# DigitalCarrierJack.net
KiCad netlist of a schematic drawn in Altium Designer
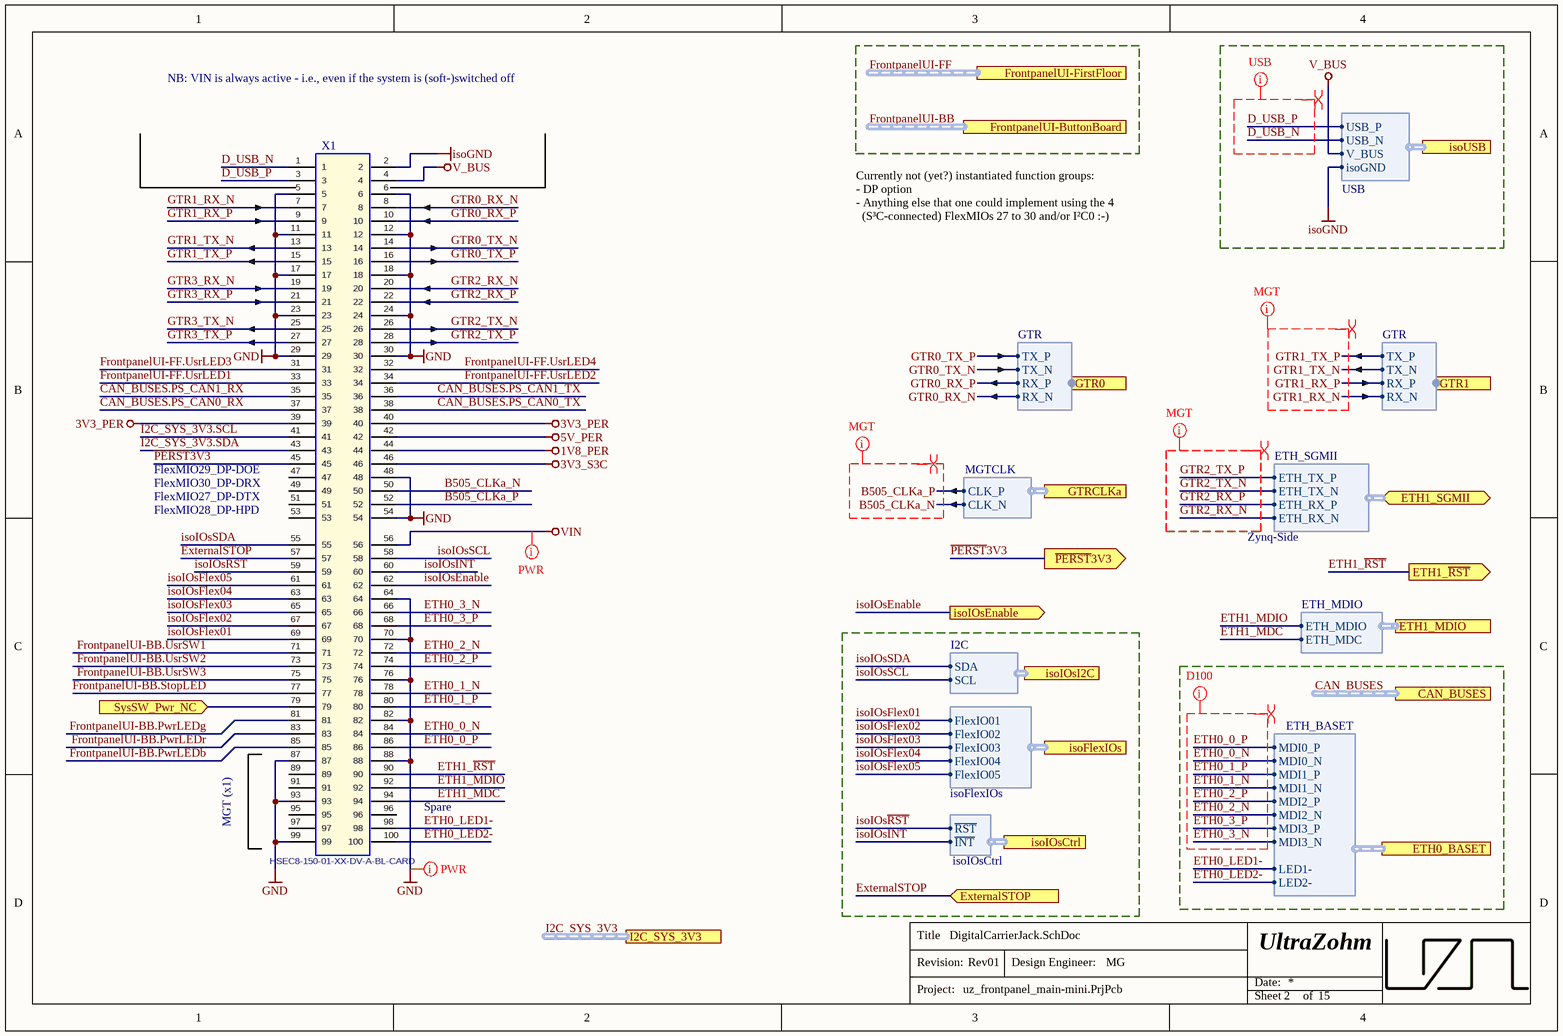
[diagram p0: DigitalCarrierJack.SchDoc]

(export (version "E")
  (design (tool "Eeschema 10.0.6"))
  (components
    (comp (ref "X1")
      (value "HSEC8-150-01-XX-DV-A-BL-CARD")
      (footprint "HSEC8-150-01-XX-DV-A-BL-CARD")
      (description "Mating Card Layout for HSEC8-150-01-XX-DV-A-BL")
      (fields (field (name "MANUFACTURER") "SAMTEC") (field (name "CREATED") "2018_04_23_AGeiger"))
      (libsource (lib "connectors") (part "HSEC8-150-01-XX-DV-A-BL-CARD"))
    )
  )
  (nets
    (net (code "14") (name "/B505_CLKa_N") (class "Default")
      (node (ref "X1") (pin "50") (pinfunction "50_50") (pintype "passive"))
    )
    (net (code "15") (name "/B505_CLKa_P") (class "Default")
      (node (ref "X1") (pin "52") (pinfunction "52_52") (pintype "passive"))
    )
    (net (code "16") (name "/CAN_BUSES.PS_CAN0_RX") (class "Default")
      (node (ref "X1") (pin "37") (pinfunction "37_37") (pintype "passive"))
    )
    (net (code "17") (name "/CAN_BUSES.PS_CAN0_TX") (class "Default")
      (node (ref "X1") (pin "38") (pinfunction "38_38") (pintype "passive"))
    )
    (net (code "18") (name "/CAN_BUSES.PS_CAN1_RX") (class "Default")
      (node (ref "X1") (pin "35") (pinfunction "35_35") (pintype "passive"))
    )
    (net (code "19") (name "/CAN_BUSES.PS_CAN1_TX") (class "Default")
      (node (ref "X1") (pin "36") (pinfunction "36_36") (pintype "passive"))
    )
    (net (code "20") (name "/D_USB_N") (class "Default")
      (node (ref "X1") (pin "1") (pinfunction "1_1") (pintype "passive"))
    )
    (net (code "21") (name "/D_USB_P") (class "Default")
      (node (ref "X1") (pin "3") (pinfunction "3_3") (pintype "passive"))
    )
    (net (code "22") (name "/ETH0_0_N") (class "Default")
      (node (ref "X1") (pin "84") (pinfunction "84_84") (pintype "passive"))
    )
    (net (code "23") (name "/ETH0_0_P") (class "Default")
      (node (ref "X1") (pin "86") (pinfunction "86_86") (pintype "passive"))
    )
    (net (code "24") (name "/ETH0_1_N") (class "Default")
      (node (ref "X1") (pin "78") (pinfunction "78_78") (pintype "passive"))
    )
    (net (code "25") (name "/ETH0_1_P") (class "Default")
      (node (ref "X1") (pin "80") (pinfunction "80_80") (pintype "passive"))
    )
    (net (code "26") (name "/ETH0_2_N") (class "Default")
      (node (ref "X1") (pin "72") (pinfunction "72_72") (pintype "passive"))
    )
    (net (code "27") (name "/ETH0_2_P") (class "Default")
      (node (ref "X1") (pin "74") (pinfunction "74_74") (pintype "passive"))
    )
    (net (code "28") (name "/ETH0_3_N") (class "Default")
      (node (ref "X1") (pin "66") (pinfunction "66_66") (pintype "passive"))
    )
    (net (code "29") (name "/ETH0_3_P") (class "Default")
      (node (ref "X1") (pin "68") (pinfunction "68_68") (pintype "passive"))
    )
    (net (code "30") (name "/ETH0_LED1-") (class "Default")
      (node (ref "X1") (pin "98") (pinfunction "98_98") (pintype "passive"))
    )
    (net (code "31") (name "/ETH0_LED2-") (class "Default")
      (node (ref "X1") (pin "100") (pinfunction "100_100") (pintype "passive"))
    )
    (net (code "32") (name "/ETH1_MDC") (class "Default")
      (node (ref "X1") (pin "94") (pinfunction "94_94") (pintype "passive"))
    )
    (net (code "33") (name "/ETH1_MDIO") (class "Default")
      (node (ref "X1") (pin "92") (pinfunction "92_92") (pintype "passive"))
    )
    (net (code "34") (name "/ETH1_~{RST}") (class "Default")
      (node (ref "X1") (pin "90") (pinfunction "90_90") (pintype "passive"))
    )
    (net (code "35") (name "/ExternalSTOP") (class "Default")
      (node (ref "X1") (pin "57") (pinfunction "57_57") (pintype "passive"))
    )
    (net (code "36") (name "/FrontpanelUI-BB.PwrLEDb") (class "Default")
      (node (ref "X1") (pin "85") (pinfunction "85_85") (pintype "passive"))
    )
    (net (code "37") (name "/FrontpanelUI-BB.PwrLEDg") (class "Default")
      (node (ref "X1") (pin "81") (pinfunction "81_81") (pintype "passive"))
    )
    (net (code "38") (name "/FrontpanelUI-BB.PwrLEDr") (class "Default")
      (node (ref "X1") (pin "83") (pinfunction "83_83") (pintype "passive"))
    )
    (net (code "39") (name "/FrontpanelUI-BB.StopLED") (class "Default")
      (node (ref "X1") (pin "77") (pinfunction "77_77") (pintype "passive"))
    )
    (net (code "40") (name "/FrontpanelUI-BB.UsrSW1") (class "Default")
      (node (ref "X1") (pin "71") (pinfunction "71_71") (pintype "passive"))
    )
    (net (code "41") (name "/FrontpanelUI-BB.UsrSW2") (class "Default")
      (node (ref "X1") (pin "73") (pinfunction "73_73") (pintype "passive"))
    )
    (net (code "42") (name "/FrontpanelUI-BB.UsrSW3") (class "Default")
      (node (ref "X1") (pin "75") (pinfunction "75_75") (pintype "passive"))
    )
    (net (code "43") (name "/FrontpanelUI-FF.UsrLED1") (class "Default")
      (node (ref "X1") (pin "33") (pinfunction "33_33") (pintype "passive"))
    )
    (net (code "44") (name "/FrontpanelUI-FF.UsrLED2") (class "Default")
      (node (ref "X1") (pin "34") (pinfunction "34_34") (pintype "passive"))
    )
    (net (code "45") (name "/FrontpanelUI-FF.UsrLED3") (class "Default")
      (node (ref "X1") (pin "31") (pinfunction "31_31") (pintype "passive"))
    )
    (net (code "46") (name "/FrontpanelUI-FF.UsrLED4") (class "Default")
      (node (ref "X1") (pin "32") (pinfunction "32_32") (pintype "passive"))
    )
    (net (code "47") (name "/GTR0_RX_N") (class "Default")
      (node (ref "X1") (pin "8") (pinfunction "8_8") (pintype "passive"))
    )
    (net (code "48") (name "/GTR0_RX_P") (class "Default")
      (node (ref "X1") (pin "10") (pinfunction "10_10") (pintype "passive"))
    )
    (net (code "49") (name "/GTR0_TX_N") (class "Default")
      (node (ref "X1") (pin "14") (pinfunction "14_14") (pintype "passive"))
    )
    (net (code "50") (name "/GTR0_TX_P") (class "Default")
      (node (ref "X1") (pin "16") (pinfunction "16_16") (pintype "passive"))
    )
    (net (code "51") (name "/GTR1_RX_N") (class "Default")
      (node (ref "X1") (pin "7") (pinfunction "7_7") (pintype "passive"))
    )
    (net (code "52") (name "/GTR1_RX_P") (class "Default")
      (node (ref "X1") (pin "9") (pinfunction "9_9") (pintype "passive"))
    )
    (net (code "53") (name "/GTR1_TX_N") (class "Default")
      (node (ref "X1") (pin "13") (pinfunction "13_13") (pintype "passive"))
    )
    (net (code "54") (name "/GTR1_TX_P") (class "Default")
      (node (ref "X1") (pin "15") (pinfunction "15_15") (pintype "passive"))
    )
    (net (code "55") (name "/GTR2_RX_N") (class "Default")
      (node (ref "X1") (pin "20") (pinfunction "20_20") (pintype "passive"))
    )
    (net (code "56") (name "/GTR2_RX_P") (class "Default")
      (node (ref "X1") (pin "22") (pinfunction "22_22") (pintype "passive"))
    )
    (net (code "57") (name "/GTR2_TX_N") (class "Default")
      (node (ref "X1") (pin "26") (pinfunction "26_26") (pintype "passive"))
    )
    (net (code "58") (name "/GTR2_TX_P") (class "Default")
      (node (ref "X1") (pin "28") (pinfunction "28_28") (pintype "passive"))
    )
    (net (code "59") (name "/GTR3_RX_N") (class "Default")
      (node (ref "X1") (pin "19") (pinfunction "19_19") (pintype "passive"))
    )
    (net (code "60") (name "/GTR3_RX_P") (class "Default")
      (node (ref "X1") (pin "21") (pinfunction "21_21") (pintype "passive"))
    )
    (net (code "61") (name "/GTR3_TX_N") (class "Default")
      (node (ref "X1") (pin "25") (pinfunction "25_25") (pintype "passive"))
    )
    (net (code "62") (name "/GTR3_TX_P") (class "Default")
      (node (ref "X1") (pin "27") (pinfunction "27_27") (pintype "passive"))
    )
    (net (code "63") (name "/I2C_SYS_3V3.SCL") (class "Default")
      (node (ref "X1") (pin "41") (pinfunction "41_41") (pintype "passive"))
    )
    (net (code "64") (name "/I2C_SYS_3V3.SDA") (class "Default")
      (node (ref "X1") (pin "43") (pinfunction "43_43") (pintype "passive"))
    )
    (net (code "65") (name "/SysSW_Pwr_NC") (class "Default")
      (node (ref "X1") (pin "79") (pinfunction "79_79") (pintype "passive"))
    )
    (net (code "66") (name "/isoIOsEnable") (class "Default")
      (node (ref "X1") (pin "62") (pinfunction "62_62") (pintype "passive"))
    )
    (net (code "67") (name "/isoIOsFlex01") (class "Default")
      (node (ref "X1") (pin "69") (pinfunction "69_69") (pintype "passive"))
    )
    (net (code "68") (name "/isoIOsFlex02") (class "Default")
      (node (ref "X1") (pin "67") (pinfunction "67_67") (pintype "passive"))
    )
    (net (code "69") (name "/isoIOsFlex03") (class "Default")
      (node (ref "X1") (pin "65") (pinfunction "65_65") (pintype "passive"))
    )
    (net (code "70") (name "/isoIOsFlex04") (class "Default")
      (node (ref "X1") (pin "63") (pinfunction "63_63") (pintype "passive"))
    )
    (net (code "71") (name "/isoIOsFlex05") (class "Default")
      (node (ref "X1") (pin "61") (pinfunction "61_61") (pintype "passive"))
    )
    (net (code "72") (name "/isoIOsSCL") (class "Default")
      (node (ref "X1") (pin "58") (pinfunction "58_58") (pintype "passive"))
    )
    (net (code "73") (name "/isoIOsSDA") (class "Default")
      (node (ref "X1") (pin "55") (pinfunction "55_55") (pintype "passive"))
    )
    (net (code "74") (name "/isoIOs~{INT}") (class "Default")
      (node (ref "X1") (pin "60") (pinfunction "60_60") (pintype "passive"))
    )
    (net (code "75") (name "/isoIOs~{RST}") (class "Default")
      (node (ref "X1") (pin "59") (pinfunction "59_59") (pintype "passive"))
    )
    (net (code "89") (name "/~{PERST}3V3") (class "Default")
      (node (ref "X1") (pin "45") (pinfunction "45_45") (pintype "passive"))
    )
    (net (code "90") (name "1V8_PER") (class "Default")
      (node (ref "X1") (pin "44") (pinfunction "44_44") (pintype "passive"))
    )
    (net (code "91") (name "3V3_PER") (class "Default")
      (node (ref "X1") (pin "39") (pinfunction "39_39") (pintype "passive"))
      (node (ref "X1") (pin "40") (pinfunction "40_40") (pintype "passive"))
    )
    (net (code "92") (name "3V3_S3C") (class "Default")
      (node (ref "X1") (pin "46") (pinfunction "46_46") (pintype "passive"))
    )
    (net (code "93") (name "5V_PER") (class "Default")
      (node (ref "X1") (pin "42") (pinfunction "42_42") (pintype "passive"))
    )
    (net (code "94") (name "GND") (class "Default")
      (node (ref "X1") (pin "11") (pinfunction "11_11") (pintype "passive"))
      (node (ref "X1") (pin "12") (pinfunction "12_12") (pintype "passive"))
      (node (ref "X1") (pin "17") (pinfunction "17_17") (pintype "passive"))
      (node (ref "X1") (pin "18") (pinfunction "18_18") (pintype "passive"))
      (node (ref "X1") (pin "23") (pinfunction "23_23") (pintype "passive"))
      (node (ref "X1") (pin "24") (pinfunction "24_24") (pintype "passive"))
      (node (ref "X1") (pin "29") (pinfunction "29_29") (pintype "passive"))
      (node (ref "X1") (pin "30") (pinfunction "30_30") (pintype "passive"))
      (node (ref "X1") (pin "48") (pinfunction "48_48") (pintype "passive"))
      (node (ref "X1") (pin "5") (pinfunction "5_5") (pintype "passive"))
      (node (ref "X1") (pin "54") (pinfunction "54_54") (pintype "passive"))
      (node (ref "X1") (pin "6") (pinfunction "6_6") (pintype "passive"))
      (node (ref "X1") (pin "64") (pinfunction "64_64") (pintype "passive"))
      (node (ref "X1") (pin "70") (pinfunction "70_70") (pintype "passive"))
      (node (ref "X1") (pin "76") (pinfunction "76_76") (pintype "passive"))
      (node (ref "X1") (pin "82") (pinfunction "82_82") (pintype "passive"))
      (node (ref "X1") (pin "87") (pinfunction "87_87") (pintype "passive"))
      (node (ref "X1") (pin "88") (pinfunction "88_88") (pintype "passive"))
      (node (ref "X1") (pin "93") (pinfunction "93_93") (pintype "passive"))
      (node (ref "X1") (pin "99") (pinfunction "99_99") (pintype "passive"))
    )
    (net (code "95") (name "VIN") (class "Default")
      (node (ref "X1") (pin "56") (pinfunction "56_56") (pintype "passive"))
    )
    (net (code "96") (name "V_BUS") (class "Default")
      (node (ref "X1") (pin "4") (pinfunction "4_4") (pintype "passive"))
    )
    (net (code "97") (name "isoGND") (class "Default")
      (node (ref "X1") (pin "2") (pinfunction "2_2") (pintype "passive"))
    )
    (net (code "98") (name "unconnected-(X1-Pad47)") (class "Default")
      (node (ref "X1") (pin "47") (pinfunction "47_47") (pintype "passive"))
    )
    (net (code "99") (name "unconnected-(X1-Pad49)") (class "Default")
      (node (ref "X1") (pin "49") (pinfunction "49_49") (pintype "passive"))
    )
    (net (code "100") (name "unconnected-(X1-Pad51)") (class "Default")
      (node (ref "X1") (pin "51") (pinfunction "51_51") (pintype "passive"))
    )
    (net (code "101") (name "unconnected-(X1-Pad53)") (class "Default")
      (node (ref "X1") (pin "53") (pinfunction "53_53") (pintype "passive"))
    )
    (net (code "102") (name "unconnected-(X1-Pad89)") (class "Default")
      (node (ref "X1") (pin "89") (pinfunction "89_89") (pintype "passive"))
    )
    (net (code "103") (name "unconnected-(X1-Pad91)") (class "Default")
      (node (ref "X1") (pin "91") (pinfunction "91_91") (pintype "passive"))
    )
    (net (code "104") (name "unconnected-(X1-Pad95)") (class "Default")
      (node (ref "X1") (pin "95") (pinfunction "95_95") (pintype "passive"))
    )
    (net (code "105") (name "unconnected-(X1-Pad96)") (class "Default")
      (node (ref "X1") (pin "96") (pinfunction "96_96") (pintype "passive"))
    )
    (net (code "106") (name "unconnected-(X1-Pad97)") (class "Default")
      (node (ref "X1") (pin "97") (pinfunction "97_97") (pintype "passive"))
    )
  )
)
